# motor_controller.net
KiCad netlist of a schematic drawn in EAGLE
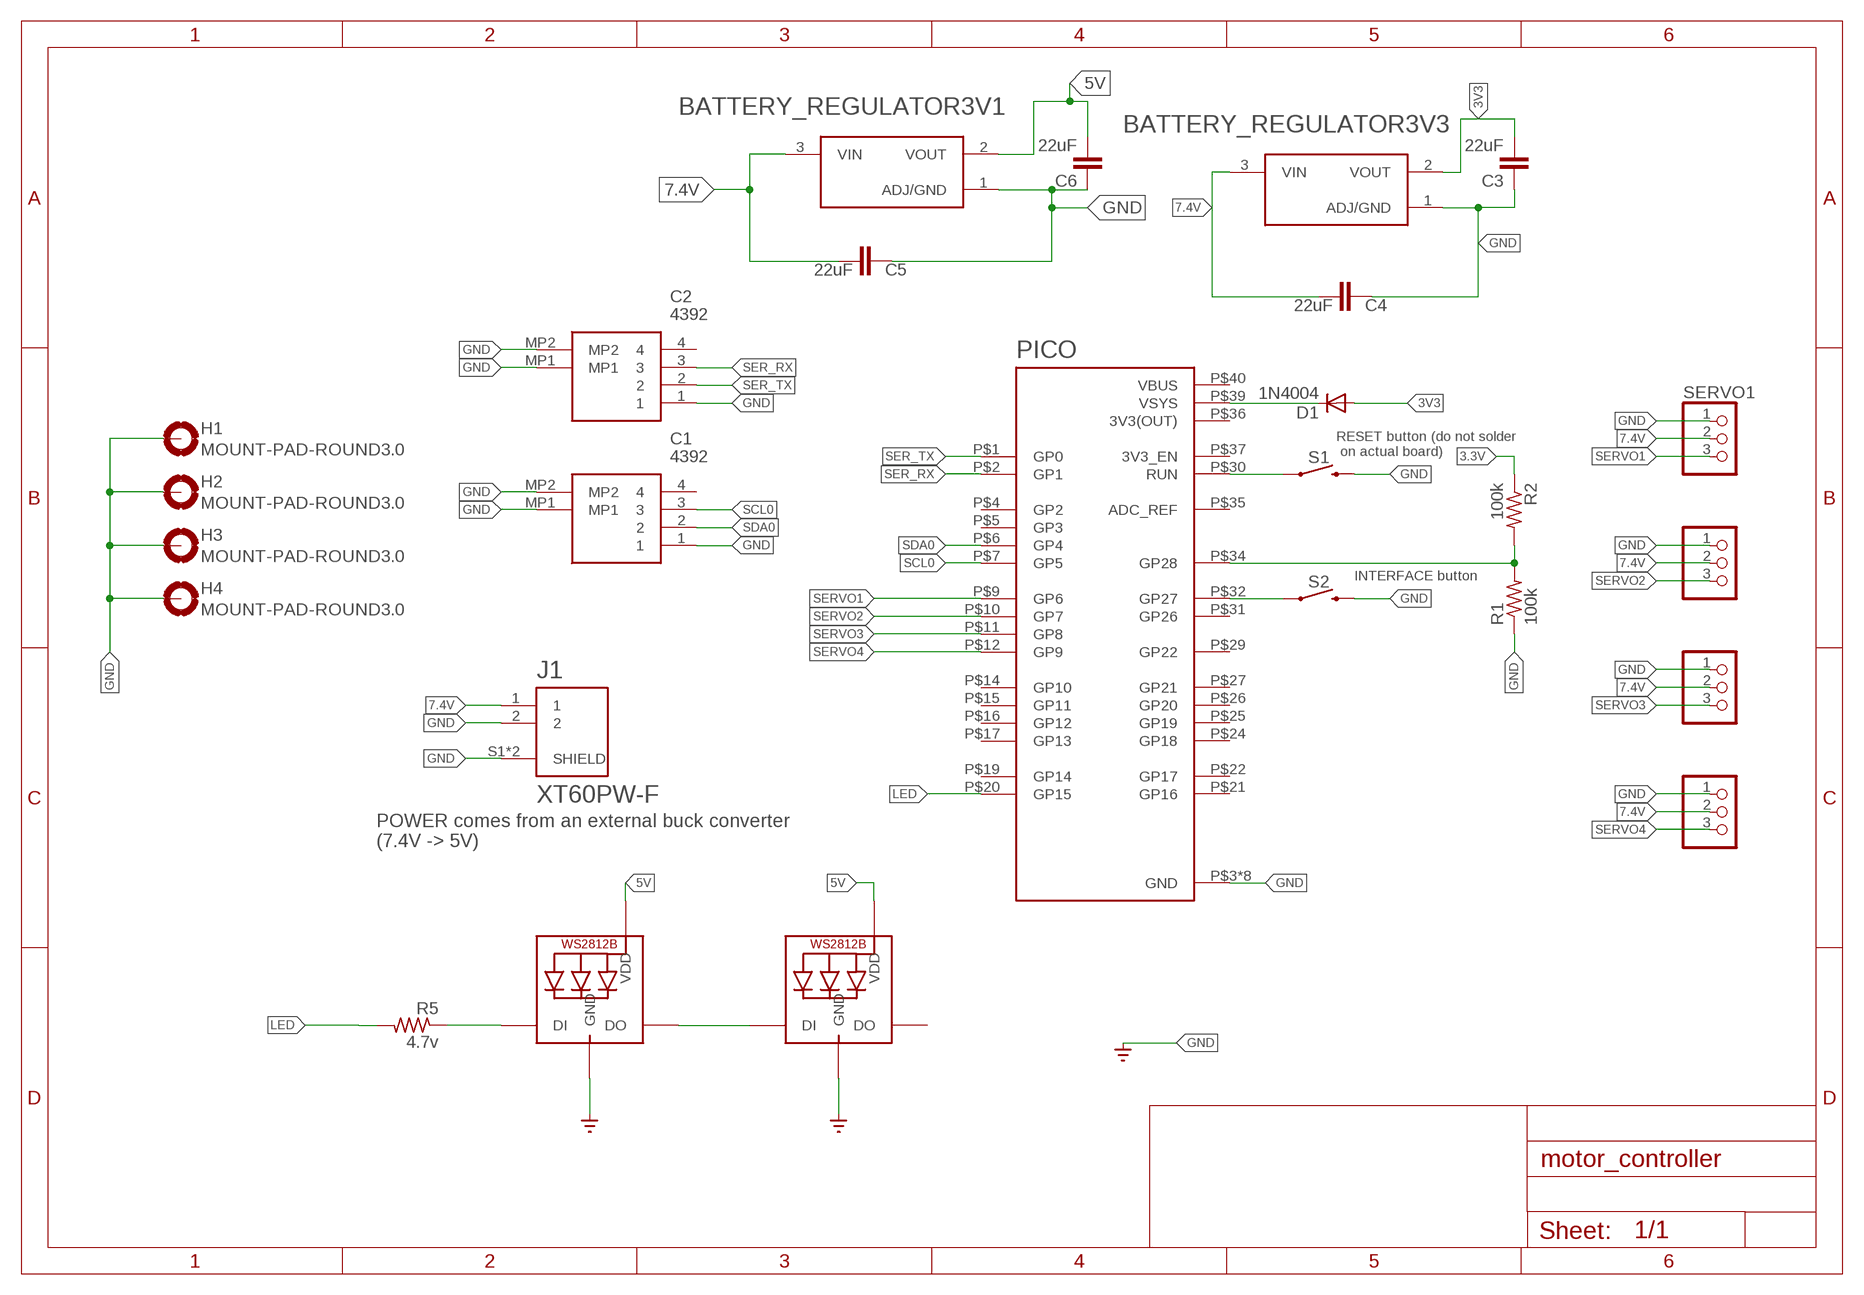
[diagram p0: schematic, sheet 1]

(export (version "E")
  (design (tool "Eeschema 10.0.6"))
  (components
    (comp (ref "BATTERY_REGULATOR3V1")
      (value "AMS1117-3.3")
      (footprint "eagle-import:SOT229P700X180-4N")
      (fields (field (name "MF") "Advanced Monolithic Systems"))
      (libsource (lib "eagle-import") (part "AMS1117-3.3"))
    )
    (comp (ref "BATTERY_REGULATOR3V3")
      (value "AMS1117-3.3")
      (footprint "eagle-import:SOT229P700X180-4N")
      (fields (field (name "MF") "Advanced Monolithic Systems"))
      (libsource (lib "eagle-import") (part "AMS1117-3.3"))
    )
    (comp (ref "C1")
      (value "4392")
      (footprint "eagle-import:4392")
      (fields (field (name "MOUSER_PART_NUMBER") "485-4392"))
      (libsource (lib "eagle-import") (part "4392"))
    )
    (comp (ref "C2")
      (value "4392")
      (footprint "eagle-import:4392")
      (fields (field (name "MOUSER_PART_NUMBER") "485-4392"))
      (libsource (lib "eagle-import") (part "4392"))
    )
    (comp (ref "C3")
      (value "22uF")
      (footprint "eagle-import:0805")
      (libsource (lib "eagle-import") (part "22UF-0805-6.3V-20%"))
    )
    (comp (ref "C4")
      (value "22uF")
      (footprint "eagle-import:0805")
      (libsource (lib "eagle-import") (part "22UF-0805-6.3V-20%"))
    )
    (comp (ref "C5")
      (value "22uF")
      (footprint "eagle-import:0805")
      (libsource (lib "eagle-import") (part "22UF-0805-6.3V-20%"))
    )
    (comp (ref "C6")
      (value "22uF")
      (footprint "eagle-import:0805")
      (libsource (lib "eagle-import") (part "22UF-0805-6.3V-20%"))
    )
    (comp (ref "D1")
      (value "1N4004")
      (footprint "eagle-import:DO41-10")
      (libsource (lib "eagle-import") (part "1N4004"))
    )
    (comp (ref "H1")
      (value "MOUNT-PAD-ROUND3.0")
      (footprint "eagle-import:3,0-PAD")
      (libsource (lib "eagle-import") (part "MOUNT-PAD-ROUND3.0"))
    )
    (comp (ref "H2")
      (value "MOUNT-PAD-ROUND3.0")
      (footprint "eagle-import:3,0-PAD")
      (libsource (lib "eagle-import") (part "MOUNT-PAD-ROUND3.0"))
    )
    (comp (ref "H3")
      (value "MOUNT-PAD-ROUND3.0")
      (footprint "eagle-import:3,0-PAD")
      (libsource (lib "eagle-import") (part "MOUNT-PAD-ROUND3.0"))
    )
    (comp (ref "H4")
      (value "MOUNT-PAD-ROUND3.0")
      (footprint "eagle-import:3,0-PAD")
      (libsource (lib "eagle-import") (part "MOUNT-PAD-ROUND3.0"))
    )
    (comp (ref "J1")
      (value "XT60PW-F")
      (footprint "eagle-import:AMASS_XT60PW-F")
      (fields (field (name "MF") "AMASS"))
      (libsource (lib "eagle-import") (part "XT60PW-F"))
    )
    (comp (ref "LED1")
      (value "WS2812B3535")
      (footprint "eagle-import:LED3535")
      (fields (field (name "MF") "Worldsemi") (field (name "MP") "WS2812B"))
      (libsource (lib "eagle-import") (part "WS2812B3535"))
    )
    (comp (ref "LED2")
      (value "WS2812B3535")
      (footprint "eagle-import:LED3535")
      (fields (field (name "MF") "Worldsemi") (field (name "MP") "WS2812B"))
      (libsource (lib "eagle-import") (part "WS2812B3535"))
    )
    (comp (ref "PICO")
      (value "RASPBERRY_PICO-NO_DEBUG")
      (footprint "eagle-import:PICO-PKG-NO_DEBUG")
      (libsource (lib "eagle-import") (part "RASPBERRY_PICO-NO_DEBUG"))
    )
    (comp (ref "R1")
      (value "100k")
      (footprint "eagle-import:R0805")
      (libsource (lib "eagle-import") (part "R-US_R0805"))
    )
    (comp (ref "R2")
      (value "100k")
      (footprint "eagle-import:R0805")
      (libsource (lib "eagle-import") (part "R-US_R0805"))
    )
    (comp (ref "R5")
      (value "4.7v")
      (footprint "eagle-import:R0805")
      (libsource (lib "eagle-import") (part "R-US_R0805"))
    )
    (comp (ref "S1")
      (value "MOMENTARY-SWITCH-SPST-PTH-6.0MM")
      (footprint "eagle-import:TACTILE_SWITCH_PTH_6.0MM")
      (libsource (lib "eagle-import") (part "MOMENTARY-SWITCH-SPST-PTH-6.0MM"))
    )
    (comp (ref "S2")
      (value "MOMENTARY-SWITCH-SPST-PTH-6.0MM")
      (footprint "eagle-import:TACTILE_SWITCH_PTH_6.0MM")
      (libsource (lib "eagle-import") (part "MOMENTARY-SWITCH-SPST-PTH-6.0MM"))
    )
    (comp (ref "SERVO1")
      (value "PINHD-1X3")
      (footprint "eagle-import:1X03")
      (libsource (lib "eagle-import") (part "PINHD-1X3"))
    )
    (comp (ref "SERVO2")
      (value "PINHD-1X3")
      (footprint "eagle-import:1X03")
      (libsource (lib "eagle-import") (part "PINHD-1X3"))
    )
    (comp (ref "SERVO3")
      (value "PINHD-1X3")
      (footprint "eagle-import:1X03")
      (libsource (lib "eagle-import") (part "PINHD-1X3"))
    )
    (comp (ref "SERVO4")
      (value "PINHD-1X3")
      (footprint "eagle-import:1X03")
      (libsource (lib "eagle-import") (part "PINHD-1X3"))
    )
  )
  (nets
    (net (code "1") (name "/3V3(OUT)") (class "Default")
      (node (ref "PICO") (pin "P$36") (pinfunction "3V3(OUT)_P$36") (pintype "power_in"))
    )
    (net (code "2") (name "/VBUS") (class "Default")
      (node (ref "PICO") (pin "P$40") (pinfunction "VBUS_P$40") (pintype "power_in"))
    )
    (net (code "3") (name "3.3V") (class "Default")
      (node (ref "R2") (pin "1") (pinfunction "1_1") (pintype "passive"))
    )
    (net (code "4") (name "3V3") (class "Default")
      (node (ref "BATTERY_REGULATOR3V3") (pin "2") (pinfunction "VOUT_2") (pintype "output"))
      (node (ref "C3") (pin "2") (pinfunction "2_2") (pintype "passive"))
      (node (ref "D1") (pin "A") (pinfunction "A_A") (pintype "passive"))
    )
    (net (code "5") (name "5V") (class "Default")
      (node (ref "BATTERY_REGULATOR3V1") (pin "2") (pinfunction "VOUT_2") (pintype "output"))
      (node (ref "C6") (pin "2") (pinfunction "2_2") (pintype "passive"))
      (node (ref "LED1") (pin "2") (pinfunction "VDD_2") (pintype "power_in"))
      (node (ref "LED2") (pin "2") (pinfunction "VDD_2") (pintype "power_in"))
    )
    (net (code "6") (name "7.4V") (class "Default")
      (node (ref "BATTERY_REGULATOR3V1") (pin "3") (pinfunction "VIN_3") (pintype "input"))
      (node (ref "BATTERY_REGULATOR3V3") (pin "3") (pinfunction "VIN_3") (pintype "input"))
      (node (ref "C4") (pin "2") (pinfunction "2_2") (pintype "passive"))
      (node (ref "C5") (pin "2") (pinfunction "2_2") (pintype "passive"))
      (node (ref "J1") (pin "1") (pinfunction "1_1") (pintype "passive"))
      (node (ref "SERVO1") (pin "2") (pinfunction "2_2") (pintype "passive"))
      (node (ref "SERVO2") (pin "2") (pinfunction "2_2") (pintype "passive"))
      (node (ref "SERVO3") (pin "2") (pinfunction "2_2") (pintype "passive"))
      (node (ref "SERVO4") (pin "2") (pinfunction "2_2") (pintype "passive"))
    )
    (net (code "7") (name "GND") (class "Default")
      (node (ref "BATTERY_REGULATOR3V1") (pin "1") (pinfunction "ADJ/GND_1") (pintype "power_in"))
      (node (ref "BATTERY_REGULATOR3V3") (pin "1") (pinfunction "ADJ/GND_1") (pintype "power_in"))
      (node (ref "C1") (pin "1") (pinfunction "1_1") (pintype "bidirectional"))
      (node (ref "C1") (pin "MP1") (pinfunction "MP1_MP1") (pintype "bidirectional"))
      (node (ref "C1") (pin "MP2") (pinfunction "MP2_MP2") (pintype "bidirectional"))
      (node (ref "C2") (pin "1") (pinfunction "1_1") (pintype "bidirectional"))
      (node (ref "C2") (pin "MP1") (pinfunction "MP1_MP1") (pintype "bidirectional"))
      (node (ref "C2") (pin "MP2") (pinfunction "MP2_MP2") (pintype "bidirectional"))
      (node (ref "C3") (pin "1") (pinfunction "1_1") (pintype "passive"))
      (node (ref "C4") (pin "1") (pinfunction "1_1") (pintype "passive"))
      (node (ref "C5") (pin "1") (pinfunction "1_1") (pintype "passive"))
      (node (ref "C6") (pin "1") (pinfunction "1_1") (pintype "passive"))
      (node (ref "H1") (pin "B3,0") (pinfunction "MOUNT_B3,0") (pintype "passive"))
      (node (ref "H2") (pin "B3,0") (pinfunction "MOUNT_B3,0") (pintype "passive"))
      (node (ref "H3") (pin "B3,0") (pinfunction "MOUNT_B3,0") (pintype "passive"))
      (node (ref "H4") (pin "B3,0") (pinfunction "MOUNT_B3,0") (pintype "passive"))
      (node (ref "J1") (pin "2") (pinfunction "2_2") (pintype "passive"))
      (node (ref "J1") (pin "S1") (pinfunction "SHIELD_S1") (pintype "passive"))
      (node (ref "J1") (pin "S2") (pinfunction "SHIELD_S2") (pintype "passive"))
      (node (ref "LED1") (pin "4") (pinfunction "GND_4") (pintype "power_in"))
      (node (ref "LED2") (pin "4") (pinfunction "GND_4") (pintype "power_in"))
      (node (ref "PICO") (pin "P$13") (pinfunction "GND_P$13") (pintype "power_in"))
      (node (ref "PICO") (pin "P$18") (pinfunction "GND_P$18") (pintype "power_in"))
      (node (ref "PICO") (pin "P$23") (pinfunction "GND_P$23") (pintype "power_in"))
      (node (ref "PICO") (pin "P$28") (pinfunction "GND_P$28") (pintype "power_in"))
      (node (ref "PICO") (pin "P$3") (pinfunction "GND_P$3") (pintype "power_in"))
      (node (ref "PICO") (pin "P$33") (pinfunction "GND_P$33") (pintype "power_in"))
      (node (ref "PICO") (pin "P$38") (pinfunction "GND_P$38") (pintype "power_in"))
      (node (ref "PICO") (pin "P$8") (pinfunction "GND_P$8") (pintype "power_in"))
      (node (ref "R1") (pin "1") (pinfunction "1_1") (pintype "passive"))
      (node (ref "S1") (pin "3") (pinfunction "2_3") (pintype "passive"))
      (node (ref "S2") (pin "3") (pinfunction "2_3") (pintype "passive"))
      (node (ref "SERVO1") (pin "1") (pinfunction "1_1") (pintype "passive"))
      (node (ref "SERVO2") (pin "1") (pinfunction "1_1") (pintype "passive"))
      (node (ref "SERVO3") (pin "1") (pinfunction "1_1") (pintype "passive"))
      (node (ref "SERVO4") (pin "1") (pinfunction "1_1") (pintype "passive"))
    )
    (net (code "8") (name "LED") (class "Default")
      (node (ref "PICO") (pin "P$20") (pinfunction "GP15_P$20") (pintype "bidirectional"))
      (node (ref "R5") (pin "2") (pinfunction "2_2") (pintype "passive"))
    )
    (net (code "9") (name "Net-(LED1-DI)") (class "Default")
      (node (ref "LED1") (pin "1") (pinfunction "DI_1") (pintype "input"))
      (node (ref "R5") (pin "1") (pinfunction "1_1") (pintype "passive"))
    )
    (net (code "10") (name "Net-(LED1-DO)") (class "Default")
      (node (ref "LED1") (pin "3") (pinfunction "DO_3") (pintype "output"))
      (node (ref "LED2") (pin "1") (pinfunction "DI_1") (pintype "input"))
    )
    (net (code "11") (name "Net-(PICO-GP27)") (class "Default")
      (node (ref "PICO") (pin "P$32") (pinfunction "GP27_P$32") (pintype "bidirectional"))
      (node (ref "S2") (pin "1") (pinfunction "1_1") (pintype "passive"))
    )
    (net (code "12") (name "Net-(PICO-GP28)") (class "Default")
      (node (ref "PICO") (pin "P$34") (pinfunction "GP28_P$34") (pintype "bidirectional"))
      (node (ref "R1") (pin "2") (pinfunction "2_2") (pintype "passive"))
      (node (ref "R2") (pin "2") (pinfunction "2_2") (pintype "passive"))
    )
    (net (code "13") (name "Net-(PICO-RUN)") (class "Default")
      (node (ref "PICO") (pin "P$30") (pinfunction "RUN_P$30") (pintype "input"))
      (node (ref "S1") (pin "1") (pinfunction "1_1") (pintype "passive"))
    )
    (net (code "14") (name "Net-(PICO-VSYS)") (class "Default")
      (node (ref "D1") (pin "C") (pinfunction "C_C") (pintype "passive"))
      (node (ref "PICO") (pin "P$39") (pinfunction "VSYS_P$39") (pintype "power_in"))
    )
    (net (code "15") (name "SCL0") (class "Default")
      (node (ref "C1") (pin "3") (pinfunction "3_3") (pintype "bidirectional"))
      (node (ref "PICO") (pin "P$7") (pinfunction "GP5_P$7") (pintype "bidirectional"))
    )
    (net (code "16") (name "SDA0") (class "Default")
      (node (ref "C1") (pin "2") (pinfunction "2_2") (pintype "bidirectional"))
      (node (ref "PICO") (pin "P$6") (pinfunction "GP4_P$6") (pintype "bidirectional"))
    )
    (net (code "17") (name "SERVO1") (class "Default")
      (node (ref "PICO") (pin "P$9") (pinfunction "GP6_P$9") (pintype "bidirectional"))
      (node (ref "SERVO1") (pin "3") (pinfunction "3_3") (pintype "passive"))
    )
    (net (code "18") (name "SERVO2") (class "Default")
      (node (ref "PICO") (pin "P$10") (pinfunction "GP7_P$10") (pintype "bidirectional"))
      (node (ref "SERVO2") (pin "3") (pinfunction "3_3") (pintype "passive"))
    )
    (net (code "19") (name "SERVO3") (class "Default")
      (node (ref "PICO") (pin "P$11") (pinfunction "GP8_P$11") (pintype "bidirectional"))
      (node (ref "SERVO3") (pin "3") (pinfunction "3_3") (pintype "passive"))
    )
    (net (code "20") (name "SERVO4") (class "Default")
      (node (ref "PICO") (pin "P$12") (pinfunction "GP9_P$12") (pintype "bidirectional"))
      (node (ref "SERVO4") (pin "3") (pinfunction "3_3") (pintype "passive"))
    )
    (net (code "21") (name "SER_RX") (class "Default")
      (node (ref "C2") (pin "3") (pinfunction "3_3") (pintype "bidirectional"))
      (node (ref "PICO") (pin "P$2") (pinfunction "GP1_P$2") (pintype "bidirectional"))
    )
    (net (code "22") (name "SER_TX") (class "Default")
      (node (ref "C2") (pin "2") (pinfunction "2_2") (pintype "bidirectional"))
      (node (ref "PICO") (pin "P$1") (pinfunction "GP0_P$1") (pintype "bidirectional"))
    )
    (net (code "23") (name "unconnected-(C1-Pad4)") (class "Default")
      (node (ref "C1") (pin "4") (pinfunction "4_4") (pintype "bidirectional"))
    )
    (net (code "24") (name "unconnected-(C2-Pad4)") (class "Default")
      (node (ref "C2") (pin "4") (pinfunction "4_4") (pintype "bidirectional"))
    )
    (net (code "25") (name "unconnected-(LED2-DO-Pad3)") (class "Default")
      (node (ref "LED2") (pin "3") (pinfunction "DO_3") (pintype "output"))
    )
    (net (code "26") (name "unconnected-(PICO-3V3_EN-PadP$37)") (class "Default")
      (node (ref "PICO") (pin "P$37") (pinfunction "3V3_EN_P$37") (pintype "input"))
    )
    (net (code "27") (name "unconnected-(PICO-ADC_REF-PadP$35)") (class "Default")
      (node (ref "PICO") (pin "P$35") (pinfunction "ADC_REF_P$35") (pintype "input"))
    )
    (net (code "28") (name "unconnected-(PICO-GP2-PadP$4)") (class "Default")
      (node (ref "PICO") (pin "P$4") (pinfunction "GP2_P$4") (pintype "bidirectional"))
    )
    (net (code "29") (name "unconnected-(PICO-GP3-PadP$5)") (class "Default")
      (node (ref "PICO") (pin "P$5") (pinfunction "GP3_P$5") (pintype "bidirectional"))
    )
    (net (code "30") (name "unconnected-(PICO-GP10-PadP$14)") (class "Default")
      (node (ref "PICO") (pin "P$14") (pinfunction "GP10_P$14") (pintype "bidirectional"))
    )
    (net (code "31") (name "unconnected-(PICO-GP11-PadP$15)") (class "Default")
      (node (ref "PICO") (pin "P$15") (pinfunction "GP11_P$15") (pintype "bidirectional"))
    )
    (net (code "32") (name "unconnected-(PICO-GP12-PadP$16)") (class "Default")
      (node (ref "PICO") (pin "P$16") (pinfunction "GP12_P$16") (pintype "bidirectional"))
    )
    (net (code "33") (name "unconnected-(PICO-GP13-PadP$17)") (class "Default")
      (node (ref "PICO") (pin "P$17") (pinfunction "GP13_P$17") (pintype "bidirectional"))
    )
    (net (code "34") (name "unconnected-(PICO-GP14-PadP$19)") (class "Default")
      (node (ref "PICO") (pin "P$19") (pinfunction "GP14_P$19") (pintype "bidirectional"))
    )
    (net (code "35") (name "unconnected-(PICO-GP16-PadP$21)") (class "Default")
      (node (ref "PICO") (pin "P$21") (pinfunction "GP16_P$21") (pintype "bidirectional"))
    )
    (net (code "36") (name "unconnected-(PICO-GP17-PadP$22)") (class "Default")
      (node (ref "PICO") (pin "P$22") (pinfunction "GP17_P$22") (pintype "bidirectional"))
    )
    (net (code "37") (name "unconnected-(PICO-GP18-PadP$24)") (class "Default")
      (node (ref "PICO") (pin "P$24") (pinfunction "GP18_P$24") (pintype "bidirectional"))
    )
    (net (code "38") (name "unconnected-(PICO-GP19-PadP$25)") (class "Default")
      (node (ref "PICO") (pin "P$25") (pinfunction "GP19_P$25") (pintype "bidirectional"))
    )
    (net (code "39") (name "unconnected-(PICO-GP20-PadP$26)") (class "Default")
      (node (ref "PICO") (pin "P$26") (pinfunction "GP20_P$26") (pintype "bidirectional"))
    )
    (net (code "40") (name "unconnected-(PICO-GP21-PadP$27)") (class "Default")
      (node (ref "PICO") (pin "P$27") (pinfunction "GP21_P$27") (pintype "bidirectional"))
    )
    (net (code "41") (name "unconnected-(PICO-GP22-PadP$29)") (class "Default")
      (node (ref "PICO") (pin "P$29") (pinfunction "GP22_P$29") (pintype "bidirectional"))
    )
    (net (code "42") (name "unconnected-(PICO-GP26-PadP$31)") (class "Default")
      (node (ref "PICO") (pin "P$31") (pinfunction "GP26_P$31") (pintype "bidirectional"))
    )
  )
)
